# PCBSchematic.net
KiCad netlist of a schematic drawn in Altium Designer
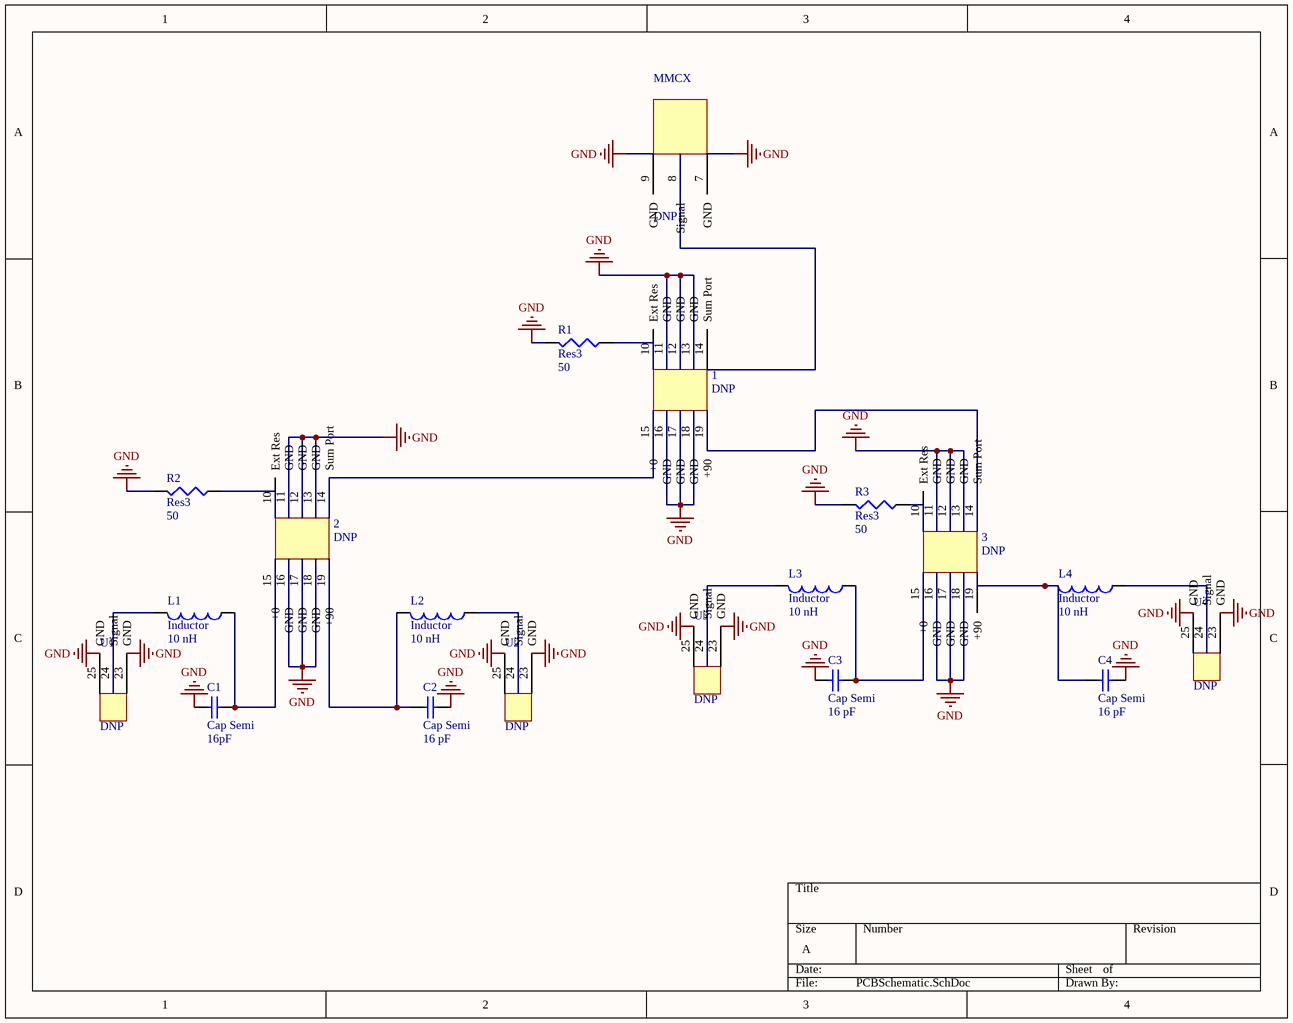
[diagram p0: PCBSchematic.SchDoc]

(export (version "E")
  (design (tool "Eeschema 10.0.6"))
  (components
    (comp (ref "1") (value "DNP") (footprint "QBA07") (libsource (lib "PCBComponents") (part "QBA-07")))
    (comp (ref "2") (value "DNP") (footprint "QBA07") (libsource (lib "PCBComponents") (part "QBA-07")))
    (comp (ref "3") (value "DNP") (footprint "QBA07") (libsource (lib "PCBComponents") (part "QBA-07")))
    (comp (ref "C1")
      (value "Cap Semi")
      (footprint "1608[0603]")
      (description "Capacitor (Semiconductor SIM Model)")
      (fields (field (name "ALTIUM_VALUE") "16pF") (field (name "PUBLISHER") "Altium Limited"))
      (libsource (lib "Miscellaneous Devices") (part "Cap Semi"))
    )
    (comp (ref "C2")
      (value "Cap Semi")
      (footprint "1608[0603]")
      (description "Capacitor (Semiconductor SIM Model)")
      (fields (field (name "ALTIUM_VALUE") "16 pF") (field (name "PUBLISHER") "Altium Limited"))
      (libsource (lib "Miscellaneous Devices") (part "Cap Semi"))
    )
    (comp (ref "C3")
      (value "Cap Semi")
      (footprint "1608[0603]")
      (description "Capacitor (Semiconductor SIM Model)")
      (fields (field (name "ALTIUM_VALUE") "16 pF") (field (name "PUBLISHER") "Altium Limited"))
      (libsource (lib "Miscellaneous Devices") (part "Cap Semi"))
    )
    (comp (ref "C4")
      (value "Cap Semi")
      (footprint "1608[0603]")
      (description "Capacitor (Semiconductor SIM Model)")
      (fields (field (name "ALTIUM_VALUE") "16 pF") (field (name "PUBLISHER") "Altium Limited"))
      (libsource (lib "Miscellaneous Devices") (part "Cap Semi"))
    )
    (comp (ref "L1")
      (value "Inductor")
      (footprint "2029")
      (fields (field (name "ALTIUM_VALUE") "10 nH") (field (name "PUBLISHER") "Altium Limited"))
      (libsource (lib "Miscellaneous Devices") (part "Inductor"))
    )
    (comp (ref "L2")
      (value "Inductor")
      (footprint "2029")
      (fields (field (name "ALTIUM_VALUE") "10 nH") (field (name "PUBLISHER") "Altium Limited"))
      (libsource (lib "Miscellaneous Devices") (part "Inductor"))
    )
    (comp (ref "L3")
      (value "Inductor")
      (footprint "2029")
      (fields (field (name "ALTIUM_VALUE") "10 nH") (field (name "PUBLISHER") "Altium Limited"))
      (libsource (lib "Miscellaneous Devices") (part "Inductor"))
    )
    (comp (ref "L4")
      (value "Inductor")
      (footprint "2029")
      (fields (field (name "ALTIUM_VALUE") "10 nH") (field (name "PUBLISHER") "Altium Limited"))
      (libsource (lib "Miscellaneous Devices") (part "Inductor"))
    )
    (comp (ref "MMCX") (value "DNP") (footprint "MMCX") (libsource (lib "PCBComponents") (part "MMCX Jack")))
    (comp (ref "R1")
      (value "Res3")
      (footprint "J1-0603")
      (description "Resistor")
      (fields (field (name "ALTIUM_VALUE") "50") (field (name "PUBLISHER") "Altium Limited"))
      (libsource (lib "Miscellaneous Devices") (part "Res3"))
    )
    (comp (ref "R2")
      (value "Res3")
      (footprint "J1-0603")
      (description "Resistor")
      (fields (field (name "ALTIUM_VALUE") "50") (field (name "PUBLISHER") "Altium Limited"))
      (libsource (lib "Miscellaneous Devices") (part "Res3"))
    )
    (comp (ref "R3")
      (value "Res3")
      (footprint "J1-0603")
      (description "Resistor")
      (fields (field (name "ALTIUM_VALUE") "50") (field (name "PUBLISHER") "Altium Limited"))
      (libsource (lib "Miscellaneous Devices") (part "Res3"))
    )
    (comp (ref "U1") (value "DNP") (footprint "U.fl") (libsource (lib "PCBComponents") (part "U.fl")))
    (comp (ref "U2") (value "DNP") (footprint "U.fl") (libsource (lib "PCBComponents") (part "U.fl")))
    (comp (ref "U3") (value "DNP") (footprint "U.fl") (libsource (lib "PCBComponents") (part "U.fl")))
    (comp (ref "U4") (value "DNP") (footprint "U.fl") (libsource (lib "PCBComponents") (part "U.fl")))
  )
  (nets
    (net (code "1") (name "GND") (class "Default")
      (node (ref "1") (pin "11") (pinfunction "GND_11") (pintype "passive"))
      (node (ref "1") (pin "12") (pinfunction "GND_12") (pintype "passive"))
      (node (ref "1") (pin "13") (pinfunction "GND_13") (pintype "passive"))
      (node (ref "1") (pin "16") (pinfunction "GND_16") (pintype "passive"))
      (node (ref "1") (pin "17") (pinfunction "GND_17") (pintype "passive"))
      (node (ref "1") (pin "18") (pinfunction "GND_18") (pintype "passive"))
      (node (ref "2") (pin "11") (pinfunction "GND_11") (pintype "passive"))
      (node (ref "2") (pin "12") (pinfunction "GND_12") (pintype "passive"))
      (node (ref "2") (pin "13") (pinfunction "GND_13") (pintype "passive"))
      (node (ref "2") (pin "16") (pinfunction "GND_16") (pintype "passive"))
      (node (ref "2") (pin "17") (pinfunction "GND_17") (pintype "passive"))
      (node (ref "2") (pin "18") (pinfunction "GND_18") (pintype "passive"))
      (node (ref "3") (pin "11") (pinfunction "GND_11") (pintype "passive"))
      (node (ref "3") (pin "12") (pinfunction "GND_12") (pintype "passive"))
      (node (ref "3") (pin "13") (pinfunction "GND_13") (pintype "passive"))
      (node (ref "3") (pin "16") (pinfunction "GND_16") (pintype "passive"))
      (node (ref "3") (pin "17") (pinfunction "GND_17") (pintype "passive"))
      (node (ref "3") (pin "18") (pinfunction "GND_18") (pintype "passive"))
      (node (ref "C1") (pin "2") (pinfunction "2_2") (pintype "passive"))
      (node (ref "C2") (pin "1") (pinfunction "1_1") (pintype "passive"))
      (node (ref "C3") (pin "2") (pinfunction "2_2") (pintype "passive"))
      (node (ref "C4") (pin "1") (pinfunction "1_1") (pintype "passive"))
      (node (ref "MMCX") (pin "7") (pinfunction "GND_7") (pintype "passive"))
      (node (ref "MMCX") (pin "9") (pinfunction "GND_9") (pintype "passive"))
      (node (ref "R1") (pin "2") (pinfunction "2_2") (pintype "passive"))
      (node (ref "R2") (pin "2") (pinfunction "2_2") (pintype "passive"))
      (node (ref "R3") (pin "2") (pinfunction "2_2") (pintype "passive"))
    )
    (net (code "2") (name "Net-(1-+0)") (class "Default")
      (node (ref "1") (pin "15") (pinfunction "+0_15") (pintype "passive"))
      (node (ref "2") (pin "14") (pinfunction "Sum_Port_14") (pintype "passive"))
    )
    (net (code "3") (name "Net-(1-+90)") (class "Default")
      (node (ref "1") (pin "19") (pinfunction "+90_19") (pintype "passive"))
      (node (ref "3") (pin "14") (pinfunction "Sum_Port_14") (pintype "passive"))
    )
    (net (code "4") (name "Net-(1-Ext_Res)") (class "Default")
      (node (ref "1") (pin "10") (pinfunction "Ext_Res_10") (pintype "passive"))
      (node (ref "R1") (pin "1") (pinfunction "1_1") (pintype "passive"))
    )
    (net (code "5") (name "Net-(1-Sum_Port)") (class "Default")
      (node (ref "1") (pin "14") (pinfunction "Sum_Port_14") (pintype "passive"))
      (node (ref "MMCX") (pin "8") (pinfunction "Signal_8") (pintype "passive"))
    )
    (net (code "6") (name "Net-(2-+0)") (class "Default")
      (node (ref "2") (pin "15") (pinfunction "+0_15") (pintype "passive"))
      (node (ref "C1") (pin "1") (pinfunction "1_1") (pintype "passive"))
      (node (ref "L1") (pin "1") (pinfunction "1_1") (pintype "passive"))
    )
    (net (code "7") (name "Net-(2-+90)") (class "Default")
      (node (ref "2") (pin "19") (pinfunction "+90_19") (pintype "passive"))
      (node (ref "C2") (pin "2") (pinfunction "2_2") (pintype "passive"))
      (node (ref "L2") (pin "2") (pinfunction "2_2") (pintype "passive"))
    )
    (net (code "8") (name "Net-(2-Ext_Res)") (class "Default")
      (node (ref "2") (pin "10") (pinfunction "Ext_Res_10") (pintype "passive"))
      (node (ref "R2") (pin "1") (pinfunction "1_1") (pintype "passive"))
    )
    (net (code "9") (name "Net-(3-+0)") (class "Default")
      (node (ref "3") (pin "15") (pinfunction "+0_15") (pintype "passive"))
      (node (ref "C3") (pin "1") (pinfunction "1_1") (pintype "passive"))
      (node (ref "L3") (pin "1") (pinfunction "1_1") (pintype "passive"))
    )
    (net (code "10") (name "Net-(3-+90)") (class "Default")
      (node (ref "3") (pin "19") (pinfunction "+90_19") (pintype "passive"))
      (node (ref "C4") (pin "2") (pinfunction "2_2") (pintype "passive"))
      (node (ref "L4") (pin "2") (pinfunction "2_2") (pintype "passive"))
    )
    (net (code "11") (name "Net-(3-Ext_Res)") (class "Default")
      (node (ref "3") (pin "10") (pinfunction "Ext_Res_10") (pintype "passive"))
      (node (ref "R3") (pin "1") (pinfunction "1_1") (pintype "passive"))
    )
    (net (code "12") (name "Net-(U1-Signal)") (class "Default")
      (node (ref "L1") (pin "2") (pinfunction "2_2") (pintype "passive"))
      (node (ref "U1") (pin "24") (pinfunction "Signal_24") (pintype "passive"))
    )
    (net (code "13") (name "Net-(U2-Signal)") (class "Default")
      (node (ref "L2") (pin "1") (pinfunction "1_1") (pintype "passive"))
      (node (ref "U2") (pin "24") (pinfunction "Signal_24") (pintype "passive"))
    )
    (net (code "14") (name "Net-(U3-Signal)") (class "Default")
      (node (ref "L3") (pin "2") (pinfunction "2_2") (pintype "passive"))
      (node (ref "U3") (pin "24") (pinfunction "Signal_24") (pintype "passive"))
    )
    (net (code "15") (name "Net-(U4-Signal)") (class "Default")
      (node (ref "L4") (pin "1") (pinfunction "1_1") (pintype "passive"))
      (node (ref "U4") (pin "24") (pinfunction "Signal_24") (pintype "passive"))
    )
    (net (code "16") (name "unconnected-(U1-GND-Pad23)") (class "Default")
      (node (ref "U1") (pin "23") (pinfunction "GND_23") (pintype "passive"))
    )
    (net (code "17") (name "unconnected-(U1-GND-Pad25)") (class "Default")
      (node (ref "U1") (pin "25") (pinfunction "GND_25") (pintype "passive"))
    )
    (net (code "18") (name "unconnected-(U2-GND-Pad23)") (class "Default")
      (node (ref "U2") (pin "23") (pinfunction "GND_23") (pintype "passive"))
    )
    (net (code "19") (name "unconnected-(U2-GND-Pad25)") (class "Default")
      (node (ref "U2") (pin "25") (pinfunction "GND_25") (pintype "passive"))
    )
    (net (code "20") (name "unconnected-(U3-GND-Pad23)") (class "Default")
      (node (ref "U3") (pin "23") (pinfunction "GND_23") (pintype "passive"))
    )
    (net (code "21") (name "unconnected-(U3-GND-Pad25)") (class "Default")
      (node (ref "U3") (pin "25") (pinfunction "GND_25") (pintype "passive"))
    )
    (net (code "22") (name "unconnected-(U4-GND-Pad23)") (class "Default")
      (node (ref "U4") (pin "23") (pinfunction "GND_23") (pintype "passive"))
    )
    (net (code "23") (name "unconnected-(U4-GND-Pad25)") (class "Default")
      (node (ref "U4") (pin "25") (pinfunction "GND_25") (pintype "passive"))
    )
  )
)
